# Input-Output.net
KiCad netlist of a schematic drawn in Altium Designer
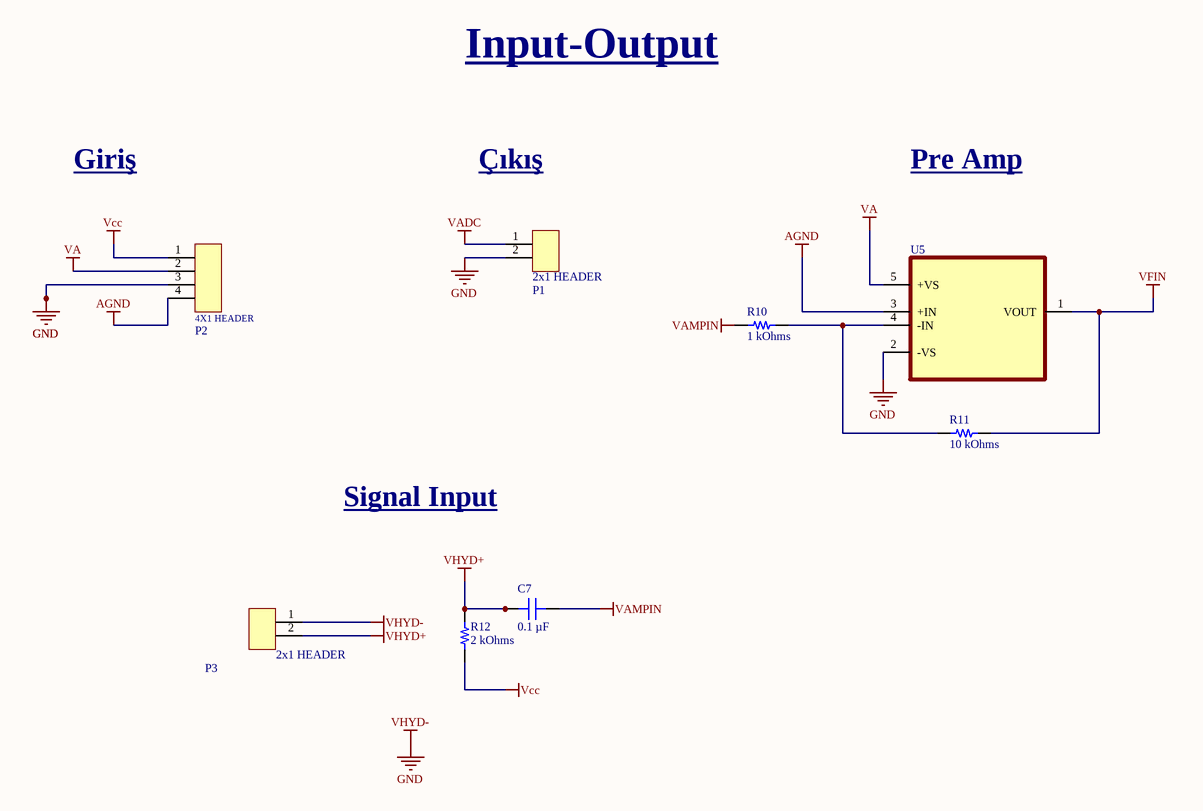
[diagram p0: Input-Output.SchDoc]

(export (version "E")
  (design (tool "Eeschema 10.0.6"))
  (components
    (comp (ref "C7")
      (value "0.1 µF")
      (footprint "CAP 0805_2012 RF")
      (description "CAP CER 0.1UF 50V X7R 0805")
      (fields (field (name "PART NUMBER") "CC0805MRX7R9BB104") (field (name "MANUFACTURER") "Yageo"))
      (libsource (lib "Celestial Altium Library - altium_library") (part "Capacitor"))
    )
    (comp (ref "P1")
      (value "WIRE-TO BOARD WAFER, 2.5MM, 2 CO")
      (footprint "51025-02-0100-01")
      (description "Connector Header Through Hole 2 position 0.098\" (2.50mm)")
      (fields
        (field (name "MANUFACTURER") "CNC Tech")
        (field (name "MANUFACTURER PART NUMBER") "51025-02-0100-01")
      )
      (libsource (lib "libv1") (part "51025-02-0100-01"))
    )
    (comp (ref "P2")
      (value "WIRE-TO BOARD HEADER, 2.5MM, 4 C")
      (footprint "51125-04-0200-01")
      (description "Wire-to Board Header, 2.5MM, 4 C")
      (fields
        (field (name "MANUFACTURER") "CNC Tech")
        (field (name "MANUFACTURER PART NUMBER") "51125-04-0200-01")
      )
      (libsource (lib "libv1") (part "51125-04-0200-01"))
    )
    (comp (ref "P3")
      (value "WIRE-TO BOARD WAFER, 2.5MM, 2 CO")
      (footprint "51025-02-0100-01")
      (description "Connector Header Through Hole 2 position 0.098\" (2.50mm)")
      (fields
        (field (name "MANUFACTURER") "CNC Tech")
        (field (name "MANUFACTURER PART NUMBER") "51025-02-0100-01")
      )
      (libsource (lib "") (part "51025-02-0100-01_1"))
    )
    (comp (ref "R10")
      (value "1 kOhms")
      (footprint "RES 1206_3216 RF")
      (description "RES SMD 1K OHM 5% 1/3W 0805")
      (fields
        (field (name "PART NUMBER") "CRGH0805J1K0")
        (field (name "MANUFACTURER") "TE Connectivity Passive Product")
      )
      (libsource (lib "Celestial Altium Library - altium_library") (part "Resistor"))
    )
    (comp (ref "R11")
      (value "10 kOhms")
      (footprint "RES 1206_3216 RF")
      (description "RES 10K OHM 0.5% 1/8W 0805")
      (fields
        (field (name "PART NUMBER") "RNCF0805DTE10K0")
        (field (name "MANUFACTURER") "Stackpole Electronics Inc")
      )
      (libsource (lib "Celestial Altium Library - altium_library") (part "Resistor"))
    )
    (comp (ref "R12")
      (value "2 kOhms")
      (footprint "RES 1206_3216 RF")
      (description "RES SMD 2K OHM 1% 0.4W 0805")
      (fields (field (name "PART NUMBER") "RCS08052K00FKEA") (field (name "MANUFACTURER") "Vishay Dale"))
      (libsource (lib "Celestial Altium Library - altium_library") (part "Resistor"))
    )
    (comp (ref "U5")
      (value "~")
      (footprint "SOT95P290X145-5N")
      (description "Voltage Feedback Amplifier 1 Circuit Rail-to-Rail SOT-23-5")
      (fields (field (name "MF") "Analog Devices") (field (name "MP") "AD8065ARTZ-REEL7"))
      (libsource (lib "AD8065ARTZ-REEL7") (part "AD8065ARTZ-REEL7"))
    )
  )
  (nets
    (net (code "1") (name "AGND") (class "Default")
      (node (ref "P2") (pin "4") (pinfunction "6_4") (pintype "passive"))
      (node (ref "U5") (pin "3") (pinfunction "+IN_3") (pintype "passive"))
    )
    (net (code "2") (name "GND") (class "Default")
      (node (ref "P1") (pin "2") (pintype "passive"))
      (node (ref "P2") (pin "3") (pinfunction "7_3") (pintype "passive"))
      (node (ref "P3") (pin "1") (pintype "passive"))
      (node (ref "U5") (pin "2") (pinfunction "-VS_2") (pintype "power_in"))
    )
    (net (code "3") (name "Net-(U5--IN)") (class "Default")
      (node (ref "R10") (pin "2") (pinfunction "2_2") (pintype "passive"))
      (node (ref "R11") (pin "1") (pinfunction "1_1") (pintype "passive"))
      (node (ref "U5") (pin "4") (pinfunction "-IN_4") (pintype "passive"))
    )
    (net (code "4") (name "VA") (class "Default")
      (node (ref "P2") (pin "2") (pinfunction "8_2") (pintype "passive"))
      (node (ref "U5") (pin "5") (pinfunction "+VS_5") (pintype "power_in"))
    )
    (net (code "5") (name "VADC") (class "Default") (node (ref "P1") (pin "1") (pintype "passive")))
    (net (code "6") (name "VAMPIN") (class "Default")
      (node (ref "C7") (pin "2") (pinfunction "2_2") (pintype "passive"))
      (node (ref "R10") (pin "1") (pinfunction "1_1") (pintype "passive"))
    )
    (net (code "7") (name "VFIN") (class "Default")
      (node (ref "R11") (pin "2") (pinfunction "2_2") (pintype "passive"))
      (node (ref "U5") (pin "1") (pinfunction "VOUT_1") (pintype "passive"))
    )
    (net (code "8") (name "VHYD+") (class "Default")
      (node (ref "C7") (pin "1") (pinfunction "1_1") (pintype "passive"))
      (node (ref "P3") (pin "2") (pintype "passive"))
      (node (ref "R12") (pin "2") (pinfunction "2_2") (pintype "passive"))
    )
    (net (code "9") (name "Vcc") (class "Default")
      (node (ref "P2") (pin "1") (pintype "passive"))
      (node (ref "R12") (pin "1") (pinfunction "1_1") (pintype "passive"))
    )
  )
)
